# LEDS.net
KiCad netlist of a schematic drawn in Altium Designer
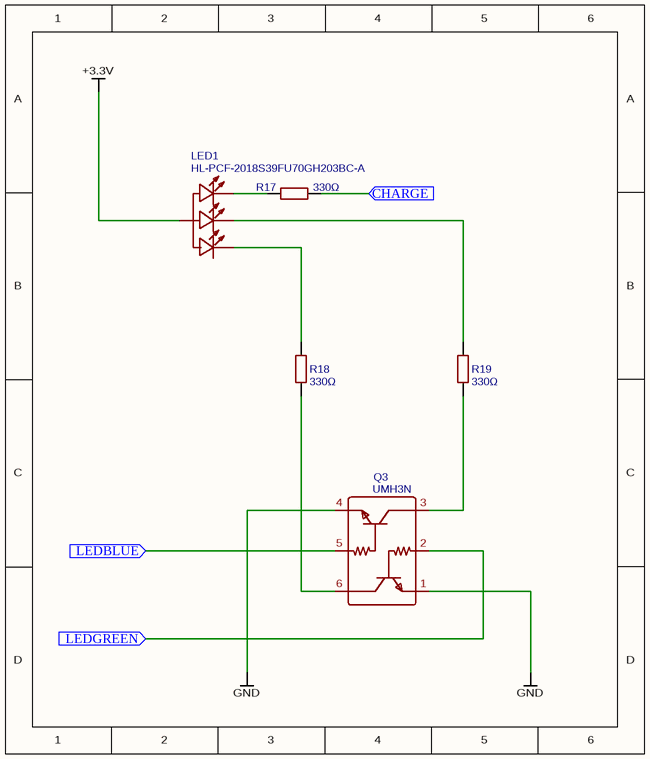
[diagram p0: LEDS.schdoc]

(export (version "E")
  (design (tool "Eeschema 10.0.6"))
  (components
    (comp (ref "LED1")
      (value "HL-PCF-2018S39FU70GH203BC-A")
      (fields (field (name "BOM_SUPPLIER PART") "C513367") (field (name "CONTRIBUTOR") "LCSC"))
      (libsource (lib "altium-import") (part "root_2_HL-PCF-2018S39FU70GH203BC-A_"))
    )
    (comp (ref "Q3")
      (value "UMH3N")
      (fields (field (name "BOM_SUPPLIER PART") "C62892"))
      (libsource (lib "altium-import") (part "root_1_UMH3N_"))
    )
    (comp (ref "R17")
      (value "330Ω")
      (fields
        (field (name "BOM_MANUFACTURER PART") "RS-03K331FT")
        (field (name "BOM_SUPPLIER PART") "C125768")
        (field (name "CONTRIBUTOR") "LCSC")
      )
      (libsource (lib "altium-import") (part "root_2_330Ω_"))
    )
    (comp (ref "R18")
      (value "330Ω")
      (fields
        (field (name "BOM_MANUFACTURER PART") "RS-03K331FT")
        (field (name "BOM_SUPPLIER PART") "C125768")
        (field (name "CONTRIBUTOR") "LCSC")
      )
      (libsource (lib "altium-import") (part "root_1_330Ω_"))
    )
    (comp (ref "R19")
      (value "330Ω")
      (fields
        (field (name "BOM_MANUFACTURER PART") "RS-03K331FT")
        (field (name "BOM_SUPPLIER PART") "C125768")
        (field (name "CONTRIBUTOR") "LCSC")
      )
      (libsource (lib "altium-import") (part "root_1_330Ω_"))
    )
  )
  (nets
    (net (code "1") (name "+3.3V") (class "Default")
      (node (ref "LED1") (pin "2") (pinfunction "A_2") (pintype "passive"))
    )
    (net (code "2") (name "/CHARGE") (class "Default")
      (node (ref "R17") (pin "1") (pinfunction "1_1") (pintype "passive"))
    )
    (net (code "3") (name "/LEDBLUE") (class "Default")
      (node (ref "Q3") (pin "5") (pinfunction "B_5") (pintype "passive"))
    )
    (net (code "4") (name "/LEDGREEN") (class "Default")
      (node (ref "Q3") (pin "2") (pinfunction "B_2") (pintype "passive"))
    )
    (net (code "5") (name "GND") (class "Default")
      (node (ref "Q3") (pin "1") (pinfunction "E_1") (pintype "passive"))
      (node (ref "Q3") (pin "4") (pinfunction "E_4") (pintype "passive"))
    )
    (net (code "6") (name "Net-(LED1-C-Pad1)") (class "Default")
      (node (ref "LED1") (pin "1") (pinfunction "C_1") (pintype "passive"))
      (node (ref "R18") (pin "2") (pinfunction "2_2") (pintype "passive"))
    )
    (net (code "7") (name "Net-(LED1-C-Pad3)") (class "Default")
      (node (ref "LED1") (pin "3") (pinfunction "C_3") (pintype "passive"))
      (node (ref "R17") (pin "2") (pinfunction "2_2") (pintype "passive"))
    )
    (net (code "8") (name "Net-(LED1-C-Pad4)") (class "Default")
      (node (ref "LED1") (pin "4") (pinfunction "C_4") (pintype "passive"))
      (node (ref "R19") (pin "2") (pinfunction "2_2") (pintype "passive"))
    )
    (net (code "9") (name "Net-(Q3-C-Pad3)") (class "Default")
      (node (ref "Q3") (pin "3") (pinfunction "C_3") (pintype "passive"))
      (node (ref "R19") (pin "1") (pinfunction "1_1") (pintype "passive"))
    )
    (net (code "10") (name "Net-(Q3-C-Pad6)") (class "Default")
      (node (ref "Q3") (pin "6") (pinfunction "C_6") (pintype "passive"))
      (node (ref "R18") (pin "1") (pinfunction "1_1") (pintype "passive"))
    )
  )
)
